# R405X.net
KiCad netlist of a schematic drawn in EAGLE
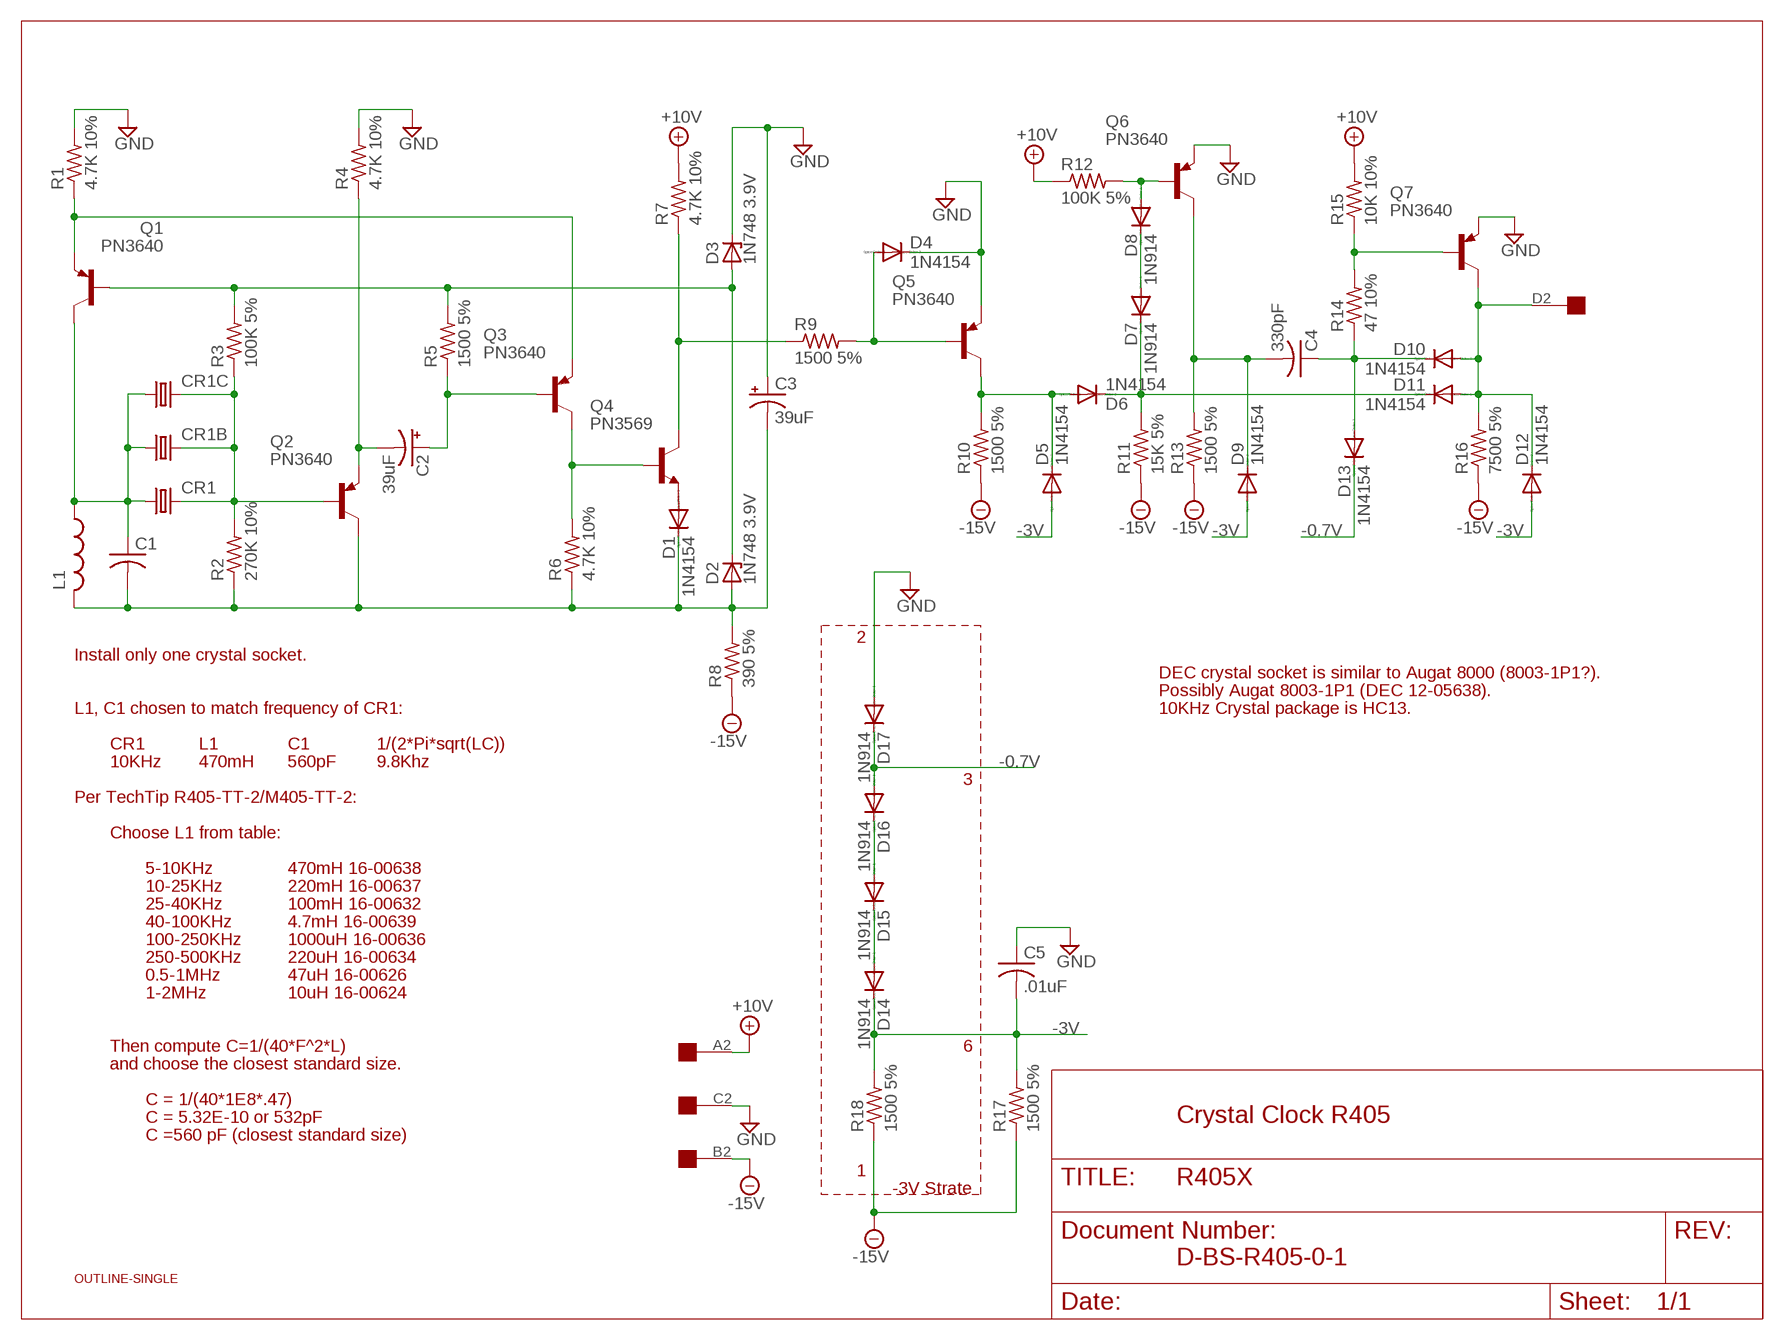
[diagram p0: schematic, sheet 1]

(export (version "E")
  (design (tool "Eeschema 10.0.6"))
  (components
    (comp (ref "C1")
      (value "C-US150-054X183")
      (footprint "eagle-import:C150-054X183")
      (libsource (lib "eagle-import") (part "C-US150-054X183"))
    )
    (comp (ref "C2")
      (value "39uF")
      (footprint "eagle-import:E15-5")
      (libsource (lib "eagle-import") (part "CPOL-USE15-5AXIAL"))
    )
    (comp (ref "C3")
      (value "39uF")
      (footprint "eagle-import:E15-5")
      (libsource (lib "eagle-import") (part "CPOL-USE15-5AXIAL"))
    )
    (comp (ref "C4")
      (value "330pF")
      (footprint "eagle-import:C150-054X183")
      (libsource (lib "eagle-import") (part "C-US150-054X183"))
    )
    (comp (ref "C5")
      (value ".01uF")
      (footprint "eagle-import:C150-054X183")
      (libsource (lib "eagle-import") (part "C-US150-054X183"))
    )
    (comp (ref "CR1")
      (value "CRYSTALHC13U-H")
      (footprint "eagle-import:HC13U-H")
      (libsource (lib "eagle-import") (part "CRYSTALHC13U-H"))
    )
    (comp (ref "CR1B")
      (value "CRYSTALSMALL")
      (footprint "eagle-import:AUG8004")
      (libsource (lib "eagle-import") (part "CRYSTALSMALL"))
    )
    (comp (ref "CR1C")
      (value "CRYSTALBIG")
      (footprint "eagle-import:AUG8000")
      (libsource (lib "eagle-import") (part "CRYSTALBIG"))
    )
    (comp (ref "D1")
      (value "1N4154")
      (footprint "eagle-import:DO35-10")
      (libsource (lib "eagle-import") (part "1N4148DO35-10"))
    )
    (comp (ref "D2")
      (value "1N748 3.9V")
      (footprint "eagle-import:DO35Z10")
      (libsource (lib "eagle-import") (part "ZENER-DIODEDO35Z10"))
    )
    (comp (ref "D3")
      (value "1N748 3.9V")
      (footprint "eagle-import:DO35Z10")
      (libsource (lib "eagle-import") (part "ZENER-DIODEDO35Z10"))
    )
    (comp (ref "D4")
      (value "1N4154")
      (footprint "eagle-import:DO35-10")
      (libsource (lib "eagle-import") (part "1N4148DO35-10"))
    )
    (comp (ref "D5")
      (value "1N4154")
      (footprint "eagle-import:DO35-10")
      (libsource (lib "eagle-import") (part "1N4148DO35-10"))
    )
    (comp (ref "D6")
      (value "1N4154")
      (footprint "eagle-import:DO35-10")
      (libsource (lib "eagle-import") (part "1N4148DO35-10"))
    )
    (comp (ref "D7")
      (value "1N914")
      (footprint "eagle-import:DO35-10")
      (libsource (lib "eagle-import") (part "1N4148DO35-10"))
    )
    (comp (ref "D8")
      (value "1N914")
      (footprint "eagle-import:DO35-10")
      (libsource (lib "eagle-import") (part "1N4148DO35-10"))
    )
    (comp (ref "D9")
      (value "1N4154")
      (footprint "eagle-import:DO35-10")
      (libsource (lib "eagle-import") (part "1N4148DO35-10"))
    )
    (comp (ref "D10")
      (value "1N4154")
      (footprint "eagle-import:DO35-10")
      (libsource (lib "eagle-import") (part "1N4148DO35-10"))
    )
    (comp (ref "D11")
      (value "1N4154")
      (footprint "eagle-import:DO35-10")
      (libsource (lib "eagle-import") (part "1N4148DO35-10"))
    )
    (comp (ref "D12")
      (value "1N4154")
      (footprint "eagle-import:DO35-10")
      (libsource (lib "eagle-import") (part "1N4148DO35-10"))
    )
    (comp (ref "D13")
      (value "1N4154")
      (footprint "eagle-import:DO35-10")
      (libsource (lib "eagle-import") (part "1N4148DO35-10"))
    )
    (comp (ref "D14")
      (value "1N914")
      (footprint "eagle-import:DO35-10")
      (libsource (lib "eagle-import") (part "1N4148DO35-10"))
    )
    (comp (ref "D15")
      (value "1N914")
      (footprint "eagle-import:DO35-10")
      (libsource (lib "eagle-import") (part "1N4148DO35-10"))
    )
    (comp (ref "D16")
      (value "1N914")
      (footprint "eagle-import:DO35-10")
      (libsource (lib "eagle-import") (part "1N4148DO35-10"))
    )
    (comp (ref "D17")
      (value "1N914")
      (footprint "eagle-import:DO35-10")
      (libsource (lib "eagle-import") (part "1N4148DO35-10"))
    )
    (comp (ref "L1")
      (value "L-US0207/7")
      (footprint "eagle-import:0207_7")
      (libsource (lib "eagle-import") (part "L-US0207/7"))
    )
    (comp (ref "Q1")
      (value "PN3640")
      (footprint "eagle-import:TO39")
      (libsource (lib "eagle-import") (part "2N2904"))
    )
    (comp (ref "Q2")
      (value "PN3640")
      (footprint "eagle-import:TO39")
      (libsource (lib "eagle-import") (part "2N2904"))
    )
    (comp (ref "Q3")
      (value "PN3640")
      (footprint "eagle-import:TO39")
      (libsource (lib "eagle-import") (part "2N2904"))
    )
    (comp (ref "Q4")
      (value "PN3569")
      (footprint "eagle-import:TO5")
      (libsource (lib "eagle-import") (part "2N2102"))
    )
    (comp (ref "Q5")
      (value "PN3640")
      (footprint "eagle-import:TO39")
      (libsource (lib "eagle-import") (part "2N2904"))
    )
    (comp (ref "Q6")
      (value "PN3640")
      (footprint "eagle-import:TO39")
      (libsource (lib "eagle-import") (part "2N2904"))
    )
    (comp (ref "Q7")
      (value "PN3640")
      (footprint "eagle-import:TO39")
      (libsource (lib "eagle-import") (part "2N2904"))
    )
    (comp (ref "R1")
      (value "4.7K 10%")
      (footprint "eagle-import:0207_10")
      (libsource (lib "eagle-import") (part "R-US_0207/10"))
    )
    (comp (ref "R2")
      (value "270K 10%")
      (footprint "eagle-import:0207_10")
      (libsource (lib "eagle-import") (part "R-US_0207/10"))
    )
    (comp (ref "R3")
      (value "100K 5%")
      (footprint "eagle-import:0207_10")
      (libsource (lib "eagle-import") (part "R-US_0207/10"))
    )
    (comp (ref "R4")
      (value "4.7K 10%")
      (footprint "eagle-import:0207_10")
      (libsource (lib "eagle-import") (part "R-US_0207/10"))
    )
    (comp (ref "R5")
      (value "1500 5%")
      (footprint "eagle-import:0207_10")
      (libsource (lib "eagle-import") (part "R-US_0207/10"))
    )
    (comp (ref "R6")
      (value "4.7K 10%")
      (footprint "eagle-import:0207_10")
      (libsource (lib "eagle-import") (part "R-US_0207/10"))
    )
    (comp (ref "R7")
      (value "4.7K 10%")
      (footprint "eagle-import:0207_10")
      (libsource (lib "eagle-import") (part "R-US_0207/10"))
    )
    (comp (ref "R8")
      (value "390 5%")
      (footprint "eagle-import:0207_10")
      (libsource (lib "eagle-import") (part "R-US_0207/10"))
    )
    (comp (ref "R9")
      (value "1500 5%")
      (footprint "eagle-import:0207_10")
      (libsource (lib "eagle-import") (part "R-US_0207/10"))
    )
    (comp (ref "R10")
      (value "1500 5%")
      (footprint "eagle-import:0207_10")
      (libsource (lib "eagle-import") (part "R-US_0207/10"))
    )
    (comp (ref "R11")
      (value "15K 5%")
      (footprint "eagle-import:0207_10")
      (libsource (lib "eagle-import") (part "R-US_0207/10"))
    )
    (comp (ref "R12")
      (value "100K 5%")
      (footprint "eagle-import:0207_10")
      (libsource (lib "eagle-import") (part "R-US_0207/10"))
    )
    (comp (ref "R13")
      (value "1500 5%")
      (footprint "eagle-import:0207_10")
      (libsource (lib "eagle-import") (part "R-US_0207/10"))
    )
    (comp (ref "R14")
      (value "47 10%")
      (footprint "eagle-import:0207_10")
      (libsource (lib "eagle-import") (part "R-US_0207/10"))
    )
    (comp (ref "R15")
      (value "10K 10%")
      (footprint "eagle-import:0207_10")
      (libsource (lib "eagle-import") (part "R-US_0207/10"))
    )
    (comp (ref "R16")
      (value "7500 5%")
      (footprint "eagle-import:0207_10")
      (libsource (lib "eagle-import") (part "R-US_0207/10"))
    )
    (comp (ref "R17")
      (value "1500 5%")
      (footprint "eagle-import:0207_10")
      (libsource (lib "eagle-import") (part "R-US_0207/10"))
    )
    (comp (ref "R18")
      (value "1500 5%")
      (footprint "eagle-import:0207_10")
      (libsource (lib "eagle-import") (part "R-US_0207/10"))
    )
    (comp (ref "U$1")
      (value "OUTLINE-SINGLE")
      (footprint "eagle-import:SINGLE")
      (libsource (lib "eagle-import") (part "OUTLINE-SINGLE"))
    )
    (comp (ref "U$2")
      (value "EDGE-1")
      (footprint "eagle-import:EDGE-CON1")
      (libsource (lib "eagle-import") (part "EDGE-1"))
    )
  )
  (nets
    (net (code "1") (name "+10V") (class "Default")
      (node (ref "R12") (pin "1") (pinfunction "1_1") (pintype "passive"))
      (node (ref "R15") (pin "2") (pinfunction "2_2") (pintype "passive"))
      (node (ref "R7") (pin "2") (pinfunction "2_2") (pintype "passive"))
      (node (ref "U$2") (pin "A2") (pinfunction "1_A2") (pintype "bidirectional"))
    )
    (net (code "2") (name "-15V") (class "Default")
      (node (ref "R10") (pin "1") (pinfunction "1_1") (pintype "passive"))
      (node (ref "R11") (pin "1") (pinfunction "1_1") (pintype "passive"))
      (node (ref "R13") (pin "1") (pinfunction "1_1") (pintype "passive"))
      (node (ref "R16") (pin "1") (pinfunction "1_1") (pintype "passive"))
      (node (ref "R17") (pin "1") (pinfunction "1_1") (pintype "passive"))
      (node (ref "R18") (pin "1") (pinfunction "1_1") (pintype "passive"))
      (node (ref "R8") (pin "1") (pinfunction "1_1") (pintype "passive"))
      (node (ref "U$2") (pin "B2") (pinfunction "1_B2") (pintype "bidirectional"))
    )
    (net (code "3") (name "/-0.7V") (class "Default")
      (node (ref "D13") (pin "C") (pinfunction "C_C") (pintype "passive"))
      (node (ref "D16") (pin "A") (pinfunction "A_A") (pintype "passive"))
      (node (ref "D17") (pin "C") (pinfunction "C_C") (pintype "passive"))
    )
    (net (code "4") (name "/-3V") (class "Default")
      (node (ref "C5") (pin "2") (pinfunction "2_2") (pintype "passive"))
      (node (ref "D12") (pin "A") (pinfunction "A_A") (pintype "passive"))
      (node (ref "D14") (pin "C") (pinfunction "C_C") (pintype "passive"))
      (node (ref "D5") (pin "A") (pinfunction "A_A") (pintype "passive"))
      (node (ref "D9") (pin "A") (pinfunction "A_A") (pintype "passive"))
      (node (ref "R17") (pin "2") (pinfunction "2_2") (pintype "passive"))
      (node (ref "R18") (pin "2") (pinfunction "2_2") (pintype "passive"))
    )
    (net (code "5") (name "GND") (class "Default")
      (node (ref "C3") (pin "+") (pinfunction "+_+") (pintype "passive"))
      (node (ref "C5") (pin "1") (pinfunction "1_1") (pintype "passive"))
      (node (ref "D17") (pin "A") (pinfunction "A_A") (pintype "passive"))
      (node (ref "D3") (pin "C") (pinfunction "C_C") (pintype "passive"))
      (node (ref "D4") (pin "C") (pinfunction "C_C") (pintype "passive"))
      (node (ref "Q5") (pin "1") (pinfunction "E_1") (pintype "passive"))
      (node (ref "Q6") (pin "1") (pinfunction "E_1") (pintype "passive"))
      (node (ref "Q7") (pin "1") (pinfunction "E_1") (pintype "passive"))
      (node (ref "R1") (pin "2") (pinfunction "2_2") (pintype "passive"))
      (node (ref "R4") (pin "2") (pinfunction "2_2") (pintype "passive"))
      (node (ref "U$2") (pin "C2") (pinfunction "1_C2") (pintype "bidirectional"))
    )
    (net (code "6") (name "Net-(C4-Pad1)") (class "Default")
      (node (ref "C4") (pin "1") (pinfunction "1_1") (pintype "passive"))
      (node (ref "D10") (pin "C") (pinfunction "C_C") (pintype "passive"))
      (node (ref "D13") (pin "A") (pinfunction "A_A") (pintype "passive"))
      (node (ref "R14") (pin "1") (pinfunction "1_1") (pintype "passive"))
    )
    (net (code "7") (name "Net-(D7-PadA)") (class "Default")
      (node (ref "D7") (pin "A") (pinfunction "A_A") (pintype "passive"))
      (node (ref "D8") (pin "C") (pinfunction "C_C") (pintype "passive"))
    )
    (net (code "8") (name "Net-(D11-PadC)") (class "Default")
      (node (ref "D11") (pin "C") (pinfunction "C_C") (pintype "passive"))
      (node (ref "D6") (pin "C") (pinfunction "C_C") (pintype "passive"))
      (node (ref "D7") (pin "C") (pinfunction "C_C") (pintype "passive"))
      (node (ref "R11") (pin "2") (pinfunction "2_2") (pintype "passive"))
    )
    (net (code "9") (name "Net-(D14-PadA)") (class "Default")
      (node (ref "D14") (pin "A") (pinfunction "A_A") (pintype "passive"))
      (node (ref "D15") (pin "C") (pinfunction "C_C") (pintype "passive"))
    )
    (net (code "10") (name "Net-(D15-PadA)") (class "Default")
      (node (ref "D15") (pin "A") (pinfunction "A_A") (pintype "passive"))
      (node (ref "D16") (pin "C") (pinfunction "C_C") (pintype "passive"))
    )
    (net (code "11") (name "Net-(Q1-B)") (class "Default")
      (node (ref "D2") (pin "C") (pinfunction "C_C") (pintype "passive"))
      (node (ref "D3") (pin "A") (pinfunction "A_A") (pintype "passive"))
      (node (ref "Q1") (pin "2") (pinfunction "B_2") (pintype "passive"))
      (node (ref "R3") (pin "2") (pinfunction "2_2") (pintype "passive"))
      (node (ref "R5") (pin "2") (pinfunction "2_2") (pintype "passive"))
    )
    (net (code "12") (name "Net-(Q1-C)") (class "Default")
      (node (ref "C1") (pin "1") (pinfunction "1_1") (pintype "passive"))
      (node (ref "CR1") (pin "1") (pinfunction "1_1") (pintype "passive"))
      (node (ref "CR1B") (pin "1") (pinfunction "1_1") (pintype "passive"))
      (node (ref "CR1C") (pin "1") (pinfunction "1_1") (pintype "passive"))
      (node (ref "L1") (pin "1") (pinfunction "1_1") (pintype "passive"))
      (node (ref "Q1") (pin "3") (pinfunction "C_3") (pintype "passive"))
    )
    (net (code "13") (name "Net-(Q1-E)") (class "Default")
      (node (ref "Q1") (pin "1") (pinfunction "E_1") (pintype "passive"))
      (node (ref "Q3") (pin "1") (pinfunction "E_1") (pintype "passive"))
      (node (ref "R1") (pin "1") (pinfunction "1_1") (pintype "passive"))
    )
    (net (code "14") (name "Net-(Q2-B)") (class "Default")
      (node (ref "CR1") (pin "2") (pinfunction "2_2") (pintype "passive"))
      (node (ref "CR1B") (pin "2") (pinfunction "2_2") (pintype "passive"))
      (node (ref "CR1C") (pin "2") (pinfunction "2_2") (pintype "passive"))
      (node (ref "Q2") (pin "2") (pinfunction "B_2") (pintype "passive"))
      (node (ref "R2") (pin "2") (pinfunction "2_2") (pintype "passive"))
      (node (ref "R3") (pin "1") (pinfunction "1_1") (pintype "passive"))
    )
    (net (code "15") (name "Net-(Q2-C)") (class "Default")
      (node (ref "C1") (pin "2") (pinfunction "2_2") (pintype "passive"))
      (node (ref "C3") (pin "-") (pinfunction "-_-") (pintype "passive"))
      (node (ref "D1") (pin "C") (pinfunction "C_C") (pintype "passive"))
      (node (ref "D2") (pin "A") (pinfunction "A_A") (pintype "passive"))
      (node (ref "L1") (pin "2") (pinfunction "2_2") (pintype "passive"))
      (node (ref "Q2") (pin "3") (pinfunction "C_3") (pintype "passive"))
      (node (ref "R2") (pin "1") (pinfunction "1_1") (pintype "passive"))
      (node (ref "R6") (pin "1") (pinfunction "1_1") (pintype "passive"))
      (node (ref "R8") (pin "2") (pinfunction "2_2") (pintype "passive"))
    )
    (net (code "16") (name "Net-(Q2-E)") (class "Default")
      (node (ref "C2") (pin "-") (pinfunction "-_-") (pintype "passive"))
      (node (ref "Q2") (pin "1") (pinfunction "E_1") (pintype "passive"))
      (node (ref "R4") (pin "1") (pinfunction "1_1") (pintype "passive"))
    )
    (net (code "17") (name "Net-(Q3-B)") (class "Default")
      (node (ref "C2") (pin "+") (pinfunction "+_+") (pintype "passive"))
      (node (ref "Q3") (pin "2") (pinfunction "B_2") (pintype "passive"))
      (node (ref "R5") (pin "1") (pinfunction "1_1") (pintype "passive"))
    )
    (net (code "18") (name "Net-(Q3-C)") (class "Default")
      (node (ref "Q3") (pin "3") (pinfunction "C_3") (pintype "passive"))
      (node (ref "Q4") (pin "2") (pinfunction "B_2") (pintype "passive"))
      (node (ref "R6") (pin "2") (pinfunction "2_2") (pintype "passive"))
    )
    (net (code "19") (name "Net-(Q4-C)") (class "Default")
      (node (ref "Q4") (pin "3") (pinfunction "C_3") (pintype "passive"))
      (node (ref "R7") (pin "1") (pinfunction "1_1") (pintype "passive"))
      (node (ref "R9") (pin "1") (pinfunction "1_1") (pintype "passive"))
    )
    (net (code "20") (name "Net-(Q4-E)") (class "Default")
      (node (ref "D1") (pin "A") (pinfunction "A_A") (pintype "passive"))
      (node (ref "Q4") (pin "1") (pinfunction "E_1") (pintype "passive"))
    )
    (net (code "21") (name "Net-(Q5-B)") (class "Default")
      (node (ref "D4") (pin "A") (pinfunction "A_A") (pintype "passive"))
      (node (ref "Q5") (pin "2") (pinfunction "B_2") (pintype "passive"))
      (node (ref "R9") (pin "2") (pinfunction "2_2") (pintype "passive"))
    )
    (net (code "22") (name "Net-(Q5-C)") (class "Default")
      (node (ref "D5") (pin "C") (pinfunction "C_C") (pintype "passive"))
      (node (ref "D6") (pin "A") (pinfunction "A_A") (pintype "passive"))
      (node (ref "Q5") (pin "3") (pinfunction "C_3") (pintype "passive"))
      (node (ref "R10") (pin "2") (pinfunction "2_2") (pintype "passive"))
    )
    (net (code "23") (name "Net-(Q6-B)") (class "Default")
      (node (ref "D8") (pin "A") (pinfunction "A_A") (pintype "passive"))
      (node (ref "Q6") (pin "2") (pinfunction "B_2") (pintype "passive"))
      (node (ref "R12") (pin "2") (pinfunction "2_2") (pintype "passive"))
    )
    (net (code "24") (name "Net-(Q6-C)") (class "Default")
      (node (ref "C4") (pin "2") (pinfunction "2_2") (pintype "passive"))
      (node (ref "D9") (pin "C") (pinfunction "C_C") (pintype "passive"))
      (node (ref "Q6") (pin "3") (pinfunction "C_3") (pintype "passive"))
      (node (ref "R13") (pin "2") (pinfunction "2_2") (pintype "passive"))
    )
    (net (code "25") (name "Net-(Q7-B)") (class "Default")
      (node (ref "Q7") (pin "2") (pinfunction "B_2") (pintype "passive"))
      (node (ref "R14") (pin "2") (pinfunction "2_2") (pintype "passive"))
      (node (ref "R15") (pin "1") (pinfunction "1_1") (pintype "passive"))
    )
    (net (code "26") (name "Net-(Q7-C)") (class "Default")
      (node (ref "D10") (pin "A") (pinfunction "A_A") (pintype "passive"))
      (node (ref "D11") (pin "A") (pinfunction "A_A") (pintype "passive"))
      (node (ref "D12") (pin "C") (pinfunction "C_C") (pintype "passive"))
      (node (ref "Q7") (pin "3") (pinfunction "C_3") (pintype "passive"))
      (node (ref "R16") (pin "2") (pinfunction "2_2") (pintype "passive"))
      (node (ref "U$2") (pin "D2") (pinfunction "1_D2") (pintype "bidirectional"))
    )
  )
)
